# MCU.net
KiCad netlist of a schematic drawn in Altium Designer
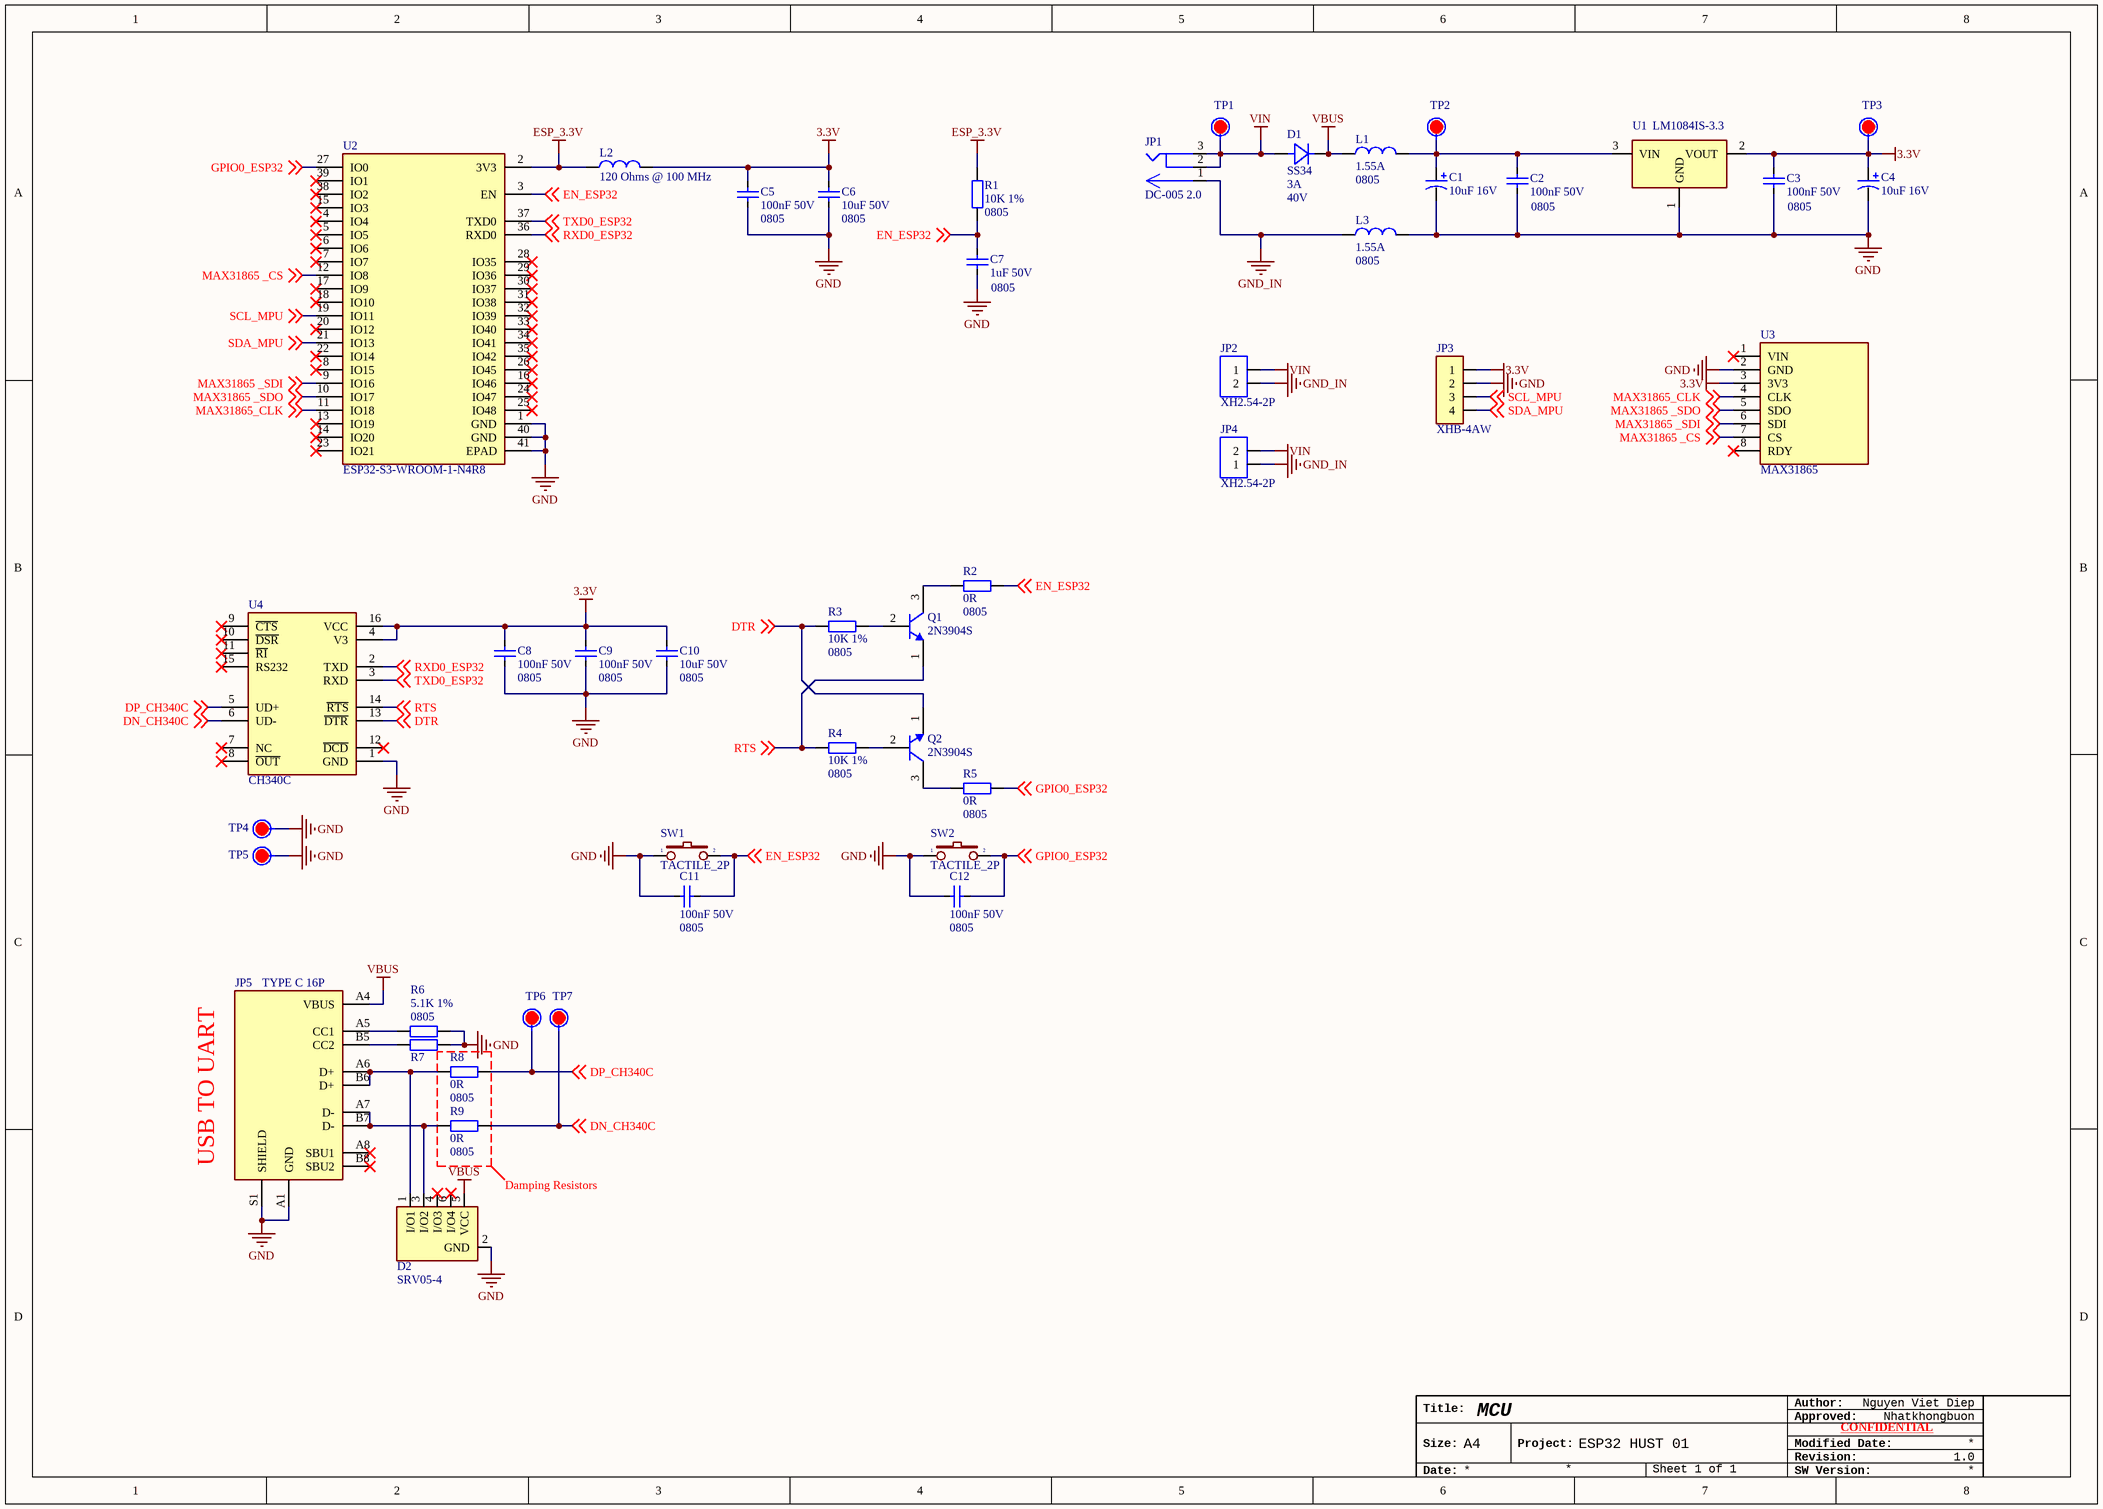
[diagram p0: MCU.SchDoc]

(export (version "E")
  (design (tool "Eeschema 10.0.6"))
  (components
    (comp (ref "C1")
      (value "10uF 16V")
      (footprint "CAP-ALU-SMD-B -NEW")
      (description "10uF 16V 14mA@120Hz ±20% SMD,D4xL5.4mm Aluminum Electrolytic Capacitors - SMD ROHS")
      (fields (field (name "MANUFACTURER") "KNSCHA") (field (name "MANUFACTURE PART NUMBER") "RST10UF16V013"))
      (libsource (lib "Capacitors") (part "C_ALU_10uF_16V_B"))
    )
    (comp (ref "C2")
      (value "100nF 50V")
      (footprint "CAP_SMD_0805_NEW")
      (description "0.1 µF ±10% 50V Ceramic Capacitor X7R 0805 (2012 Metric)")
      (fields
        (field (name "MANUFACTURER") "YAGEO")
        (field (name "MANUFACTURE PART NUMBER") "CC0805KRX7R9BB104")
        (field (name "SIZE") "0805")
      )
      (libsource (lib "Capacitors") (part "C0805_MLCC_100nF_50V"))
    )
    (comp (ref "C3")
      (value "100nF 50V")
      (footprint "CAP_SMD_0805_NEW")
      (description "0.1 µF ±10% 50V Ceramic Capacitor X7R 0805 (2012 Metric)")
      (fields
        (field (name "MANUFACTURER") "YAGEO")
        (field (name "MANUFACTURE PART NUMBER") "CC0805KRX7R9BB104")
        (field (name "SIZE") "0805")
      )
      (libsource (lib "Capacitors") (part "C0805_MLCC_100nF_50V"))
    )
    (comp (ref "C4")
      (value "10uF 16V")
      (footprint "CAP-ALU-SMD-B -NEW")
      (description "10uF 16V 14mA@120Hz ±20% SMD,D4xL5.4mm Aluminum Electrolytic Capacitors - SMD ROHS")
      (fields (field (name "MANUFACTURER") "KNSCHA") (field (name "MANUFACTURE PART NUMBER") "RST10UF16V013"))
      (libsource (lib "Capacitors") (part "C_ALU_10uF_16V_B"))
    )
    (comp (ref "C5")
      (value "100nF 50V")
      (footprint "CAP_SMD_0805_NEW")
      (description "0.1 µF ±10% 50V Ceramic Capacitor X7R 0805 (2012 Metric)")
      (fields
        (field (name "MANUFACTURER") "YAGEO")
        (field (name "MANUFACTURE PART NUMBER") "CC0805KRX7R9BB104")
        (field (name "SIZE") "0805")
      )
      (libsource (lib "Capacitors") (part "C0805_MLCC_100nF_50V"))
    )
    (comp (ref "C6")
      (value "10uF 50V")
      (footprint "CAP_SMD_0805_NEW")
      (description "10 µF ±20% 50V Ceramic Capacitor X5R 0805 (2012 Metric)")
      (fields
        (field (name "MANUFACTURER") "Murata Electronics")
        (field (name "MANUFACTURE PART NUMBER") "GRM21BR61H106ME43L")
        (field (name "SIZE") "0805")
      )
      (libsource (lib "Capacitors") (part "C0805_MLCC_10uF_50V"))
    )
    (comp (ref "C7")
      (value "1uF 50V")
      (footprint "CAP_SMD_0805_NEW")
      (description "1 µF ±10% 50V Ceramic Capacitor X7R 0805 (2012 Metric)")
      (fields
        (field (name "MANUFACTURER") "Samsung Electro-Mechanics")
        (field (name "MANUFACTURE PART NUMBER") "CL21B105KBFNNNG")
        (field (name "SIZE") "0805")
      )
      (libsource (lib "Capacitors") (part "C0805_MLCC_1uF_50V"))
    )
    (comp (ref "C8")
      (value "100nF 50V")
      (footprint "CAP_SMD_0805_NEW")
      (description "0.1 µF ±10% 50V Ceramic Capacitor X7R 0805 (2012 Metric)")
      (fields
        (field (name "MANUFACTURER") "YAGEO")
        (field (name "MANUFACTURE PART NUMBER") "CC0805KRX7R9BB104")
        (field (name "SIZE") "0805")
      )
      (libsource (lib "Capacitors") (part "C0805_MLCC_100nF_50V"))
    )
    (comp (ref "C9")
      (value "100nF 50V")
      (footprint "CAP_SMD_0805_NEW")
      (description "0.1 µF ±10% 50V Ceramic Capacitor X7R 0805 (2012 Metric)")
      (fields
        (field (name "MANUFACTURER") "YAGEO")
        (field (name "MANUFACTURE PART NUMBER") "CC0805KRX7R9BB104")
        (field (name "SIZE") "0805")
      )
      (libsource (lib "Capacitors") (part "C0805_MLCC_100nF_50V"))
    )
    (comp (ref "C10")
      (value "10uF 50V")
      (footprint "CAP_SMD_0805_NEW")
      (description "10 µF ±20% 50V Ceramic Capacitor X5R 0805 (2012 Metric)")
      (fields
        (field (name "MANUFACTURER") "Murata Electronics")
        (field (name "MANUFACTURE PART NUMBER") "GRM21BR61H106ME43L")
        (field (name "SIZE") "0805")
      )
      (libsource (lib "Capacitors") (part "C0805_MLCC_10uF_50V"))
    )
    (comp (ref "C11")
      (value "100nF 50V")
      (footprint "CAP_SMD_0805_NEW")
      (description "0.1 µF ±10% 50V Ceramic Capacitor X7R 0805 (2012 Metric)")
      (fields
        (field (name "MANUFACTURER") "YAGEO")
        (field (name "MANUFACTURE PART NUMBER") "CC0805KRX7R9BB104")
        (field (name "SIZE") "0805")
      )
      (libsource (lib "Capacitors") (part "C0805_MLCC_100nF_50V"))
    )
    (comp (ref "C12")
      (value "100nF 50V")
      (footprint "CAP_SMD_0805_NEW")
      (description "0.1 µF ±10% 50V Ceramic Capacitor X7R 0805 (2012 Metric)")
      (fields
        (field (name "MANUFACTURER") "YAGEO")
        (field (name "MANUFACTURE PART NUMBER") "CC0805KRX7R9BB104")
        (field (name "SIZE") "0805")
      )
      (libsource (lib "Capacitors") (part "C0805_MLCC_100nF_50V"))
    )
    (comp (ref "D1")
      (value "SS34")
      (footprint "SMA")
      (description "Diode 40 V 3A Surface Mount SMA")
      (fields
        (field (name "MANUFACTURER") "MDD")
        (field (name "CURRENT") "3A")
        (field (name "DC VOLTAGE") "40V")
      )
      (libsource (lib "Diode") (part "SS34"))
    )
    (comp (ref "D2")
      (value "SRV05-4")
      (footprint "SOT23-6")
      (description "15V Clamp 4A (8/20µs) Ipp Tvs Diode Surface Mount SOT23-6L")
      (fields (field (name "MANUFACTURER") "ANBON SEMICONDUCTOR (INT'L) LIMITED"))
      (libsource (lib "Diode") (part "TVS_SRV05-4"))
    )
    (comp (ref "JP1")
      (value "DC-005 2.0")
      (footprint "DC_POWER_JACK")
      (description "Right-Angle DC Power Receptacle 2mm 6.4mm Plugin DC Power Connector ROHS")
      (fields (field (name "MANUFACTURER") "BOOMELE(Boom Precision Elec)"))
      (libsource (lib "Connectors") (part "DC-005 2.0"))
    )
    (comp (ref "JP2")
      (value "XH2.54-2P")
      (footprint "XH_2.54_2P")
      (description "1x2P 2P XH 1 2.54mm Tin 2 -25℃~+85℃ Brass 3A Straight Plugin,P=2.54mm Wire To Board Connector ROHS")
      (fields
        (field (name "MANUFACTURER") "Megastar")
        (field (name "MANUFACTURE PART NUMBER") "ZX-XH2.54-2PZZ")
      )
      (libsource (lib "") (part "XH2.54-2P_1"))
    )
    (comp (ref "JP3")
      (value "XHB-4AW")
      (footprint "CONN_XHB-4AW")
      (description "1x4P 4P 1 2.5mm 4 Right-Angle Push-Pull,P=2.5mm Wire To Board Connector ROHS")
      (fields (field (name "MANUFACTURER") "BOOMELE(Boom Precision Elec)"))
      (libsource (lib "Connectors") (part "XHB-4AW"))
    )
    (comp (ref "JP4")
      (value "XH2.54-2P")
      (footprint "XH_2.54_2P")
      (description "1x2P 2P XH 1 2.54mm Tin 2 -25℃~+85℃ Brass 3A Straight Plugin,P=2.54mm Wire To Board Connector ROHS")
      (fields
        (field (name "MANUFACTURER") "Megastar")
        (field (name "MANUFACTURE PART NUMBER") "ZX-XH2.54-2PZZ")
      )
      (libsource (lib "Connectors") (part "XH2.54-2P"))
    )
    (comp (ref "JP5")
      (value "TYPE C 16P")
      (footprint "TYPE C 16P")
      (fields
        (field (name "MANUFACTURER") "Amphenol ICC (Commercial Products)")
        (field (name "MANUFACTURE PART NUMBER") "12402012E212A")
      )
      (libsource (lib "Connectors") (part "TYPE_C_16P"))
    )
    (comp (ref "L1")
      (value "120Ohms 100Mhz")
      (footprint "FB_0805")
      (fields
        (field (name "MANUFACTURER") "Murata Electronics")
        (field (name "MANUFACTURE PART NUMBER") "BLM21PG121BH1D")
        (field (name "CURRENT") "1.55A")
        (field (name "SIZE") "0805")
      )
      (libsource (lib "Inductors") (part "FR_120Ohms_100Mhz"))
    )
    (comp (ref "L2")
      (value "120Ohms 100Mhz")
      (footprint "FB_0805")
      (fields
        (field (name "MANUFACTURER") "Murata Electronics")
        (field (name "MANUFACTURE PART NUMBER") "BLM21PG121BH1D")
        (field (name "IMPEDANCE @ FREQUENCY") "120 Ohms @ 100 MHz")
      )
      (libsource (lib "Inductors") (part "FR_120Ohms_100Mhz"))
    )
    (comp (ref "L3")
      (value "120Ohms 100Mhz")
      (footprint "FB_0805")
      (fields
        (field (name "MANUFACTURER") "Murata Electronics")
        (field (name "MANUFACTURE PART NUMBER") "BLM21PG121BH1D")
        (field (name "CURRENT") "1.55A")
        (field (name "SIZE") "0805")
      )
      (libsource (lib "Inductors") (part "FR_120Ohms_100Mhz"))
    )
    (comp (ref "Q1")
      (value "2N3904S")
      (footprint "2N3904S")
      (description "40V 350mW 100@10mA,1V 200mA NPN SOT-23 Bipolar (BJT) ROHS")
      (fields
        (field (name "MANUFACTURER") "KEC Semicon")
        (field (name "MANUFACTURE PART NUMBER") "2N3904S-RTK/PS")
      )
      (libsource (lib "Trans_Fets") (part "2N3904S-RTK/PS"))
    )
    (comp (ref "Q2")
      (value "2N3904S")
      (footprint "2N3904S")
      (description "40V 350mW 100@10mA,1V 200mA NPN SOT-23 Bipolar (BJT) ROHS")
      (fields
        (field (name "MANUFACTURER") "KEC Semicon")
        (field (name "MANUFACTURE PART NUMBER") "2N3904S-RTK/PS")
      )
      (libsource (lib "Trans_Fets") (part "2N3904S-RTK/PS"))
    )
    (comp (ref "R1")
      (value "10K 1%")
      (footprint "RES_SMD_0805")
      (description "10 kOhms ±1% 0.125W, 1/8W Chip Resistor 0805 (2012 Metric) Moisture Resistant Thick Film")
      (fields
        (field (name "MANUFACTURER") "YAGEO")
        (field (name "MANUFACTURE PART NUMBER") "RC0805FR-0710KL")
        (field (name "SIZE") "0805")
      )
      (libsource (lib "Resistors") (part "R0805_10K"))
    )
    (comp (ref "R2")
      (value "0R")
      (footprint "RES_SMD_0805")
      (description "0 Ohms Jumper Chip Resistor 0805 (2012 Metric) Automotive AEC-Q200 Thick Film")
      (fields
        (field (name "MANUFACTURER") "Vishay Dale")
        (field (name "MANUFACTURE PART NUMBER") "CRCW08050000Z0EA")
        (field (name "SIZE") "0805")
      )
      (libsource (lib "Resistors") (part "R0805_0R"))
    )
    (comp (ref "R3")
      (value "10K 1%")
      (footprint "RES_SMD_0805")
      (description "10 kOhms ±1% 0.125W, 1/8W Chip Resistor 0805 (2012 Metric) Moisture Resistant Thick Film")
      (fields
        (field (name "MANUFACTURER") "YAGEO")
        (field (name "MANUFACTURE PART NUMBER") "RC0805FR-0710KL")
        (field (name "SIZE") "0805")
      )
      (libsource (lib "Resistors") (part "R0805_10K"))
    )
    (comp (ref "R4")
      (value "10K 1%")
      (footprint "RES_SMD_0805")
      (description "10 kOhms ±1% 0.125W, 1/8W Chip Resistor 0805 (2012 Metric) Moisture Resistant Thick Film")
      (fields
        (field (name "MANUFACTURER") "YAGEO")
        (field (name "MANUFACTURE PART NUMBER") "RC0805FR-0710KL")
        (field (name "SIZE") "0805")
      )
      (libsource (lib "Resistors") (part "R0805_10K"))
    )
    (comp (ref "R5")
      (value "0R")
      (footprint "RES_SMD_0805")
      (description "0 Ohms Jumper Chip Resistor 0805 (2012 Metric) Automotive AEC-Q200 Thick Film")
      (fields
        (field (name "MANUFACTURER") "Vishay Dale")
        (field (name "MANUFACTURE PART NUMBER") "CRCW08050000Z0EA")
        (field (name "SIZE") "0805")
      )
      (libsource (lib "Resistors") (part "R0805_0R"))
    )
    (comp (ref "R6")
      (value "5.1K 1%")
      (footprint "RES_SMD_0805")
      (description "5.1 kOhms ±1% 0.125W, 1/8W Chip Resistor 0805 (2012 Metric) Moisture Resistant Thick Film")
      (fields
        (field (name "MANUFACTURER") "YAGEO")
        (field (name "MANUFACTURE PART NUMBER") "RC0805FR-075K1L")
        (field (name "SIZE") "0805")
      )
      (libsource (lib "Resistors") (part "R0805_5.1K"))
    )
    (comp (ref "R7")
      (value "5.1K 1%")
      (footprint "RES_SMD_0805")
      (description "5.1 kOhms ±1% 0.125W, 1/8W Chip Resistor 0805 (2012 Metric) Moisture Resistant Thick Film")
      (fields
        (field (name "MANUFACTURER") "YAGEO")
        (field (name "MANUFACTURE PART NUMBER") "RC0805FR-075K1L")
      )
      (libsource (lib "Resistors") (part "R0805_5.1K"))
    )
    (comp (ref "R8")
      (value "0R")
      (footprint "RES_SMD_0805")
      (description "0 Ohms Jumper Chip Resistor 0805 (2012 Metric) Automotive AEC-Q200 Thick Film")
      (fields
        (field (name "MANUFACTURER") "Vishay Dale")
        (field (name "MANUFACTURE PART NUMBER") "CRCW08050000Z0EA")
        (field (name "SIZE") "0805")
      )
      (libsource (lib "Resistors") (part "R0805_0R"))
    )
    (comp (ref "R9")
      (value "0R")
      (footprint "RES_SMD_0805")
      (description "0 Ohms Jumper Chip Resistor 0805 (2012 Metric) Automotive AEC-Q200 Thick Film")
      (fields
        (field (name "MANUFACTURER") "Vishay Dale")
        (field (name "MANUFACTURE PART NUMBER") "CRCW08050000Z0EA")
        (field (name "SIZE") "0805")
      )
      (libsource (lib "Resistors") (part "R0805_0R"))
    )
    (comp (ref "SW1")
      (value "TACTILE_2P")
      (footprint "C&K SW 2P")
      (description "Tactile Switch SPST-NO Top Actuated Surface Mount")
      (fields
        (field (name "MANUFACTURER") "C&K")
        (field (name "MANUFACTURE PART NUMBER") "PTS636 SM25F SMTR LFS")
      )
      (libsource (lib "Button") (part "SWITCH_TACTILE_SPST"))
    )
    (comp (ref "SW2")
      (value "TACTILE_2P")
      (footprint "C&K SW 2P")
      (description "Tactile Switch SPST-NO Top Actuated Surface Mount")
      (fields
        (field (name "MANUFACTURER") "C&K")
        (field (name "MANUFACTURE PART NUMBER") "PTS636 SM25F SMTR LFS")
      )
      (libsource (lib "Button") (part "SWITCH_TACTILE_SPST"))
    )
    (comp (ref "TP1")
      (value "Test Point")
      (footprint "TEST_POINT")
      (libsource (lib "Connectors") (part "TEST_POINT"))
    )
    (comp (ref "TP2")
      (value "Test Point")
      (footprint "TEST_POINT")
      (libsource (lib "Connectors") (part "TEST_POINT"))
    )
    (comp (ref "TP3")
      (value "Test Point")
      (footprint "TEST_POINT")
      (libsource (lib "Connectors") (part "TEST_POINT"))
    )
    (comp (ref "TP4")
      (value "Test Point")
      (footprint "TEST_POINT")
      (libsource (lib "Connectors") (part "TEST_POINT"))
    )
    (comp (ref "TP5")
      (value "Test Point")
      (footprint "TEST_POINT")
      (libsource (lib "Connectors") (part "TEST_POINT"))
    )
    (comp (ref "TP6")
      (value "Test Point")
      (footprint "TEST_POINT")
      (libsource (lib "Connectors") (part "TEST_POINT"))
    )
    (comp (ref "TP7")
      (value "Test Point")
      (footprint "TEST_POINT")
      (libsource (lib "Connectors") (part "TEST_POINT"))
    )
    (comp (ref "U1")
      (value "LM1084IS-3.3")
      (footprint "TO263")
      (description "Linear Voltage Regulator IC Positive Fixed 1 Output 5A TO-263 (DDPAK-3)")
      (fields
        (field (name "MANUFACTURER") "STMicroelectronics")
        (field (name "MANUFACTURE PART NUMBER") "LM1084IS-3.3/NOPB")
      )
      (libsource (lib "Voltage_Regulators") (part "LM1084IS-3.3"))
    )
    (comp (ref "U2")
      (value "ESP32-S3-WROOM-1-N4R8")
      (footprint "ESP32-S3-WROOM-1-N4R8")
      (description "Bluetooth, WiFi 802.11b/g/n, Bluetooth v5.0 Transceiver Module 2.4GHz PCB Trace Surface Mount")
      (fields (field (name "MANUFACTURER") "Espressif Systems"))
      (libsource (lib "MCU") (part "ESP32-S3-WROOM-1-N4R8"))
    )
    (comp (ref "U3")
      (value "MAX31865")
      (footprint "MAX31865 - 3")
      (description "Mạch chuyển tín hiệu RTD to Digital MAX31865 PT100/PT1000")
      (libsource (lib "Modules") (part "MAX31865"))
    )
    (comp (ref "U4")
      (value "CH340C")
      (footprint "CH340C")
      (description "2Mbps Transceiver USB 2.0 SOP-16 USB Converters ROHS")
      (fields (field (name "MANUFACTURER") "WCH(Jiangsu Qin Heng)"))
      (libsource (lib "ICs") (part "CH340C"))
    )
  )
  (nets
    (net (code "1") (name "3.3V") (class "Default")
      (node (ref "C10") (pin "2") (pinfunction "2_2") (pintype "passive"))
      (node (ref "C3") (pin "2") (pinfunction "2_2") (pintype "passive"))
      (node (ref "C4") (pin "1") (pinfunction "1_1") (pintype "passive"))
      (node (ref "C5") (pin "2") (pinfunction "2_2") (pintype "passive"))
      (node (ref "C6") (pin "2") (pinfunction "2_2") (pintype "passive"))
      (node (ref "C8") (pin "2") (pinfunction "2_2") (pintype "passive"))
      (node (ref "C9") (pin "2") (pinfunction "2_2") (pintype "passive"))
      (node (ref "JP3") (pin "1") (pinfunction "1_1") (pintype "passive"))
      (node (ref "L2") (pin "2") (pinfunction "2_2") (pintype "passive"))
      (node (ref "TP3") (pin "1") (pinfunction "1_1") (pintype "passive"))
      (node (ref "U1") (pin "2") (pinfunction "VOUT_2") (pintype "passive"))
      (node (ref "U3") (pin "3") (pinfunction "3V3_3") (pintype "passive"))
      (node (ref "U4") (pin "16") (pinfunction "VCC_16") (pintype "passive"))
      (node (ref "U4") (pin "4") (pinfunction "V3_4") (pintype "passive"))
    )
    (net (code "2") (name "DN_CH340C") (class "Default")
      (node (ref "R9") (pin "2") (pinfunction "2_2") (pintype "passive"))
      (node (ref "TP7") (pin "1") (pinfunction "1_1") (pintype "passive"))
      (node (ref "U4") (pin "6") (pinfunction "UD-_6") (pintype "passive"))
    )
    (net (code "3") (name "DP_CH340C") (class "Default")
      (node (ref "R8") (pin "2") (pinfunction "2_2") (pintype "passive"))
      (node (ref "TP6") (pin "1") (pinfunction "1_1") (pintype "passive"))
      (node (ref "U4") (pin "5") (pinfunction "UD+_5") (pintype "passive"))
    )
    (net (code "4") (name "DTR") (class "Default")
      (node (ref "Q2") (pin "1") (pinfunction "B_1") (pintype "passive"))
      (node (ref "R3") (pin "2") (pinfunction "2_2") (pintype "passive"))
      (node (ref "U4") (pin "13") (pinfunction "~{DTR}_13") (pintype "passive"))
    )
    (net (code "5") (name "EN_ESP32") (class "Default")
      (node (ref "C11") (pin "1") (pinfunction "1_1") (pintype "passive"))
      (node (ref "C7") (pin "2") (pinfunction "2_2") (pintype "passive"))
      (node (ref "R1") (pin "1") (pinfunction "1_1") (pintype "passive"))
      (node (ref "R2") (pin "2") (pinfunction "2_2") (pintype "passive"))
      (node (ref "SW1") (pin "2") (pinfunction "2_2") (pintype "passive"))
      (node (ref "U2") (pin "3") (pinfunction "EN_3") (pintype "passive"))
    )
    (net (code "6") (name "ESP_3.3V") (class "Default")
      (node (ref "L2") (pin "1") (pinfunction "1_1") (pintype "passive"))
      (node (ref "R1") (pin "2") (pinfunction "2_2") (pintype "passive"))
      (node (ref "U2") (pin "2") (pinfunction "3V3_2") (pintype "passive"))
    )
    (net (code "7") (name "GND") (class "Default")
      (node (ref "C1") (pin "2") (pinfunction "2_2") (pintype "passive"))
      (node (ref "C10") (pin "1") (pinfunction "1_1") (pintype "passive"))
      (node (ref "C11") (pin "2") (pinfunction "2_2") (pintype "passive"))
      (node (ref "C12") (pin "2") (pinfunction "2_2") (pintype "passive"))
      (node (ref "C2") (pin "1") (pinfunction "1_1") (pintype "passive"))
      (node (ref "C3") (pin "1") (pinfunction "1_1") (pintype "passive"))
      (node (ref "C4") (pin "2") (pinfunction "2_2") (pintype "passive"))
      (node (ref "C5") (pin "1") (pinfunction "1_1") (pintype "passive"))
      (node (ref "C6") (pin "1") (pinfunction "1_1") (pintype "passive"))
      (node (ref "C7") (pin "1") (pinfunction "1_1") (pintype "passive"))
      (node (ref "C8") (pin "1") (pinfunction "1_1") (pintype "passive"))
      (node (ref "C9") (pin "1") (pinfunction "1_1") (pintype "passive"))
      (node (ref "D2") (pin "2") (pinfunction "GND_2") (pintype "passive"))
      (node (ref "JP3") (pin "2") (pinfunction "2_2") (pintype "passive"))
      (node (ref "JP5") (pin "A1") (pinfunction "GND_A1") (pintype "passive"))
      (node (ref "JP5") (pin "S1") (pinfunction "SHIELD_S1") (pintype "passive"))
      (node (ref "L3") (pin "2") (pinfunction "2_2") (pintype "passive"))
      (node (ref "R6") (pin "2") (pinfunction "2_2") (pintype "passive"))
      (node (ref "R7") (pin "2") (pinfunction "2_2") (pintype "passive"))
      (node (ref "SW1") (pin "1") (pinfunction "1_1") (pintype "passive"))
      (node (ref "SW2") (pin "1") (pinfunction "1_1") (pintype "passive"))
      (node (ref "TP4") (pin "1") (pinfunction "1_1") (pintype "passive"))
      (node (ref "TP5") (pin "1") (pinfunction "1_1") (pintype "passive"))
      (node (ref "U1") (pin "1") (pinfunction "GND_1") (pintype "passive"))
      (node (ref "U2") (pin "1") (pinfunction "GND_1") (pintype "passive"))
      (node (ref "U2") (pin "40") (pinfunction "GND_40") (pintype "passive"))
      (node (ref "U2") (pin "41") (pinfunction "EPAD_41") (pintype "passive"))
      (node (ref "U3") (pin "2") (pinfunction "GND_2") (pintype "passive"))
      (node (ref "U4") (pin "1") (pinfunction "GND_1") (pintype "passive"))
    )
    (net (code "8") (name "GND_IN") (class "Default")
      (node (ref "JP1") (pin "1") (pinfunction "1_1") (pintype "passive"))
      (node (ref "JP2") (pin "2") (pinfunction "2_2") (pintype "passive"))
      (node (ref "JP4") (pin "1") (pinfunction "1_1") (pintype "passive"))
      (node (ref "L3") (pin "1") (pinfunction "1_1") (pintype "passive"))
    )
    (net (code "9") (name "GPIO0_ESP32") (class "Default")
      (node (ref "C12") (pin "1") (pinfunction "1_1") (pintype "passive"))
      (node (ref "R5") (pin "2") (pinfunction "2_2") (pintype "passive"))
      (node (ref "SW2") (pin "2") (pinfunction "2_2") (pintype "passive"))
      (node (ref "U2") (pin "27") (pinfunction "IO0_27") (pintype "passive"))
    )
    (net (code "10") (name "MAX31865 _CS") (class "Default")
      (node (ref "U2") (pin "12") (pinfunction "IO8_12") (pintype "passive"))
      (node (ref "U3") (pin "7") (pinfunction "CS_7") (pintype "passive"))
    )
    (net (code "11") (name "MAX31865 _SDI") (class "Default")
      (node (ref "U2") (pin "9") (pinfunction "IO16_9") (pintype "passive"))
      (node (ref "U3") (pin "6") (pinfunction "SDI_6") (pintype "passive"))
    )
    (net (code "12") (name "MAX31865 _SDO") (class "Default")
      (node (ref "U2") (pin "10") (pinfunction "IO17_10") (pintype "passive"))
      (node (ref "U3") (pin "5") (pinfunction "SDO_5") (pintype "passive"))
    )
    (net (code "13") (name "MAX31865_CLK") (class "Default")
      (node (ref "U2") (pin "11") (pinfunction "IO18_11") (pintype "passive"))
      (node (ref "U3") (pin "4") (pinfunction "CLK_4") (pintype "passive"))
    )
    (net (code "14") (name "Net-(D2-I{slash}O1)") (class "Default")
      (node (ref "D2") (pin "1") (pinfunction "I/O1_1") (pintype "passive"))
      (node (ref "JP5") (pin "A6") (pinfunction "D+_A6") (pintype "passive"))
      (node (ref "JP5") (pin "B6") (pinfunction "D+_B6") (pintype "passive"))
      (node (ref "R8") (pin "1") (pinfunction "1_1") (pintype "passive"))
    )
    (net (code "15") (name "Net-(D2-I{slash}O2)") (class "Default")
      (node (ref "D2") (pin "3") (pinfunction "I/O2_3") (pintype "passive"))
      (node (ref "JP5") (pin "A7") (pinfunction "D-_A7") (pintype "passive"))
      (node (ref "JP5") (pin "B7") (pinfunction "D-_B7") (pintype "passive"))
      (node (ref "R9") (pin "1") (pinfunction "1_1") (pintype "passive"))
    )
    (net (code "16") (name "Net-(JP5-CC1)") (class "Default")
      (node (ref "JP5") (pin "A5") (pinfunction "CC1_A5") (pintype "passive"))
      (node (ref "R6") (pin "1") (pinfunction "1_1") (pintype "passive"))
    )
    (net (code "17") (name "Net-(JP5-CC2)") (class "Default")
      (node (ref "JP5") (pin "B5") (pinfunction "CC2_B5") (pintype "passive"))
      (node (ref "R7") (pin "1") (pinfunction "1_1") (pintype "passive"))
    )
    (net (code "18") (name "Net-(Q1-C)") (class "Default")
      (node (ref "Q1") (pin "3") (pinfunction "C_3") (pintype "passive"))
      (node (ref "R2") (pin "1") (pinfunction "1_1") (pintype "passive"))
    )
    (net (code "19") (name "Net-(Q1-E)") (class "Default")
      (node (ref "Q1") (pin "2") (pinfunction "E_2") (pintype "passive"))
      (node (ref "R3") (pin "1") (pinfunction "1_1") (pintype "passive"))
    )
    (net (code "20") (name "Net-(Q2-C)") (class "Default")
      (node (ref "Q2") (pin "3") (pinfunction "C_3") (pintype "passive"))
      (node (ref "R5") (pin "1") (pinfunction "1_1") (pintype "passive"))
    )
    (net (code "21") (name "Net-(Q2-E)") (class "Default")
      (node (ref "Q2") (pin "2") (pinfunction "E_2") (pintype "passive"))
      (node (ref "R4") (pin "1") (pinfunction "1_1") (pintype "passive"))
    )
    (net (code "22") (name "Net-(U1-VIN)") (class "Default")
      (node (ref "C1") (pin "1") (pinfunction "1_1") (pintype "passive"))
      (node (ref "C2") (pin "2") (pinfunction "2_2") (pintype "passive"))
      (node (ref "L1") (pin "2") (pinfunction "2_2") (pintype "passive"))
      (node (ref "TP2") (pin "1") (pinfunction "1_1") (pintype "passive"))
      (node (ref "U1") (pin "3") (pinfunction "VIN_3") (pintype "passive"))
    )
    (net (code "23") (name "RTS") (class "Default")
      (node (ref "Q1") (pin "1") (pinfunction "B_1") (pintype "passive"))
      (node (ref "R4") (pin "2") (pinfunction "2_2") (pintype "passive"))
      (node (ref "U4") (pin "14") (pinfunction "~{RTS}_14") (pintype "passive"))
    )
    (net (code "24") (name "RXD0_ESP32") (class "Default")
      (node (ref "U2") (pin "36") (pinfunction "RXD0_36") (pintype "passive"))
      (node (ref "U4") (pin "2") (pinfunction "TXD_2") (pintype "passive"))
    )
    (net (code "25") (name "SCL_MPU") (class "Default")
      (node (ref "JP3") (pin "3") (pinfunction "3_3") (pintype "passive"))
      (node (ref "U2") (pin "19") (pinfunction "IO11_19") (pintype "passive"))
    )
    (net (code "26") (name "SDA_MPU") (class "Default")
      (node (ref "JP3") (pin "4") (pinfunction "4_4") (pintype "passive"))
      (node (ref "U2") (pin "21") (pinfunction "IO13_21") (pintype "passive"))
    )
    (net (code "27") (name "TXD0_ESP32") (class "Default")
      (node (ref "U2") (pin "37") (pinfunction "TXD0_37") (pintype "passive"))
      (node (ref "U4") (pin "3") (pinfunction "RXD_3") (pintype "passive"))
    )
    (net (code "28") (name "VBUS") (class "Default")
      (node (ref "D1") (pin "C") (pinfunction "C_C") (pintype "passive"))
      (node (ref "D2") (pin "5") (pinfunction "VCC_5") (pintype "passive"))
      (node (ref "JP5") (pin "A4") (pinfunction "VBUS_A4") (pintype "passive"))
      (node (ref "L1") (pin "1") (pinfunction "1_1") (pintype "passive"))
    )
    (net (code "29") (name "VIN") (class "Default")
      (node (ref "D1") (pin "A") (pinfunction "A_A") (pintype "passive"))
      (node (ref "JP1") (pin "2") (pinfunction "2_2") (pintype "passive"))
      (node (ref "JP1") (pin "3") (pinfunction "3_3") (pintype "passive"))
      (node (ref "JP2") (pin "1") (pinfunction "1_1") (pintype "passive"))
      (node (ref "JP4") (pin "2") (pinfunction "2_2") (pintype "passive"))
      (node (ref "TP1") (pin "1") (pinfunction "1_1") (pintype "passive"))
    )
    (net (code "30") (name "unconnected-(D2-I{slash}O3-Pad4)") (class "Default")
      (node (ref "D2") (pin "4") (pinfunction "I/O3_4") (pintype "passive+no_connect"))
    )
    (net (code "31") (name "unconnected-(D2-I{slash}O4-Pad6)") (class "Default")
      (node (ref "D2") (pin "6") (pinfunction "I/O4_6") (pintype "passive+no_connect"))
    )
    (net (code "32") (name "unconnected-(JP5-SBU1-PadA8)") (class "Default")
      (node (ref "JP5") (pin "A8") (pinfunction "SBU1_A8") (pintype "passive+no_connect"))
    )
    (net (code "33") (name "unconnected-(JP5-SBU2-PadB8)") (class "Default")
      (node (ref "JP5") (pin "B8") (pinfunction "SBU2_B8") (pintype "passive+no_connect"))
    )
    (net (code "34") (name "unconnected-(U2-IO1-Pad39)") (class "Default")
      (node (ref "U2") (pin "39") (pinfunction "IO1_39") (pintype "passive+no_connect"))
    )
    (net (code "35") (name "unconnected-(U2-IO2-Pad38)") (class "Default")
      (node (ref "U2") (pin "38") (pinfunction "IO2_38") (pintype "passive+no_connect"))
    )
    (net (code "36") (name "unconnected-(U2-IO3-Pad15)") (class "Default")
      (node (ref "U2") (pin "15") (pinfunction "IO3_15") (pintype "passive+no_connect"))
    )
    (net (code "37") (name "unconnected-(U2-IO4-Pad4)") (class "Default")
      (node (ref "U2") (pin "4") (pinfunction "IO4_4") (pintype "passive+no_connect"))
    )
    (net (code "38") (name "unconnected-(U2-IO5-Pad5)") (class "Default")
      (node (ref "U2") (pin "5") (pinfunction "IO5_5") (pintype "passive+no_connect"))
    )
    (net (code "39") (name "unconnected-(U2-IO6-Pad6)") (class "Default")
      (node (ref "U2") (pin "6") (pinfunction "IO6_6") (pintype "passive+no_connect"))
    )
    (net (code "40") (name "unconnected-(U2-IO7-Pad7)") (class "Default")
      (node (ref "U2") (pin "7") (pinfunction "IO7_7") (pintype "passive+no_connect"))
    )
    (net (code "41") (name "unconnected-(U2-IO9-Pad17)") (class "Default")
      (node (ref "U2") (pin "17") (pinfunction "IO9_17") (pintype "passive+no_connect"))
    )
    (net (code "42") (name "unconnected-(U2-IO10-Pad18)") (class "Default")
      (node (ref "U2") (pin "18") (pinfunction "IO10_18") (pintype "passive+no_connect"))
    )
    (net (code "43") (name "unconnected-(U2-IO12-Pad20)") (class "Default")
      (node (ref "U2") (pin "20") (pinfunction "IO12_20") (pintype "passive+no_connect"))
    )
    (net (code "44") (name "unconnected-(U2-IO14-Pad22)") (class "Default")
      (node (ref "U2") (pin "22") (pinfunction "IO14_22") (pintype "passive+no_connect"))
    )
    (net (code "45") (name "unconnected-(U2-IO15-Pad8)") (class "Default")
      (node (ref "U2") (pin "8") (pinfunction "IO15_8") (pintype "passive+no_connect"))
    )
    (net (code "46") (name "unconnected-(U2-IO19-Pad13)") (class "Default")
      (node (ref "U2") (pin "13") (pinfunction "IO19_13") (pintype "passive+no_connect"))
    )
    (net (code "47") (name "unconnected-(U2-IO20-Pad14)") (class "Default")
      (node (ref "U2") (pin "14") (pinfunction "IO20_14") (pintype "passive+no_connect"))
    )
    (net (code "48") (name "unconnected-(U2-IO21-Pad23)") (class "Default")
      (node (ref "U2") (pin "23") (pinfunction "IO21_23") (pintype "passive+no_connect"))
    )
    (net (code "49") (name "unconnected-(U2-IO35-Pad28)") (class "Default")
      (node (ref "U2") (pin "28") (pinfunction "IO35_28") (pintype "passive+no_connect"))
    )
    (net (code "50") (name "unconnected-(U2-IO36-Pad29)") (class "Default")
      (node (ref "U2") (pin "29") (pinfunction "IO36_29") (pintype "passive+no_connect"))
    )
    (net (code "51") (name "unconnected-(U2-IO37-Pad30)") (class "Default")
      (node (ref "U2") (pin "30") (pinfunction "IO37_30") (pintype "passive+no_connect"))
    )
    (net (code "52") (name "unconnected-(U2-IO38-Pad31)") (class "Default")
      (node (ref "U2") (pin "31") (pinfunction "IO38_31") (pintype "passive+no_connect"))
    )
    (net (code "53") (name "unconnected-(U2-IO39-Pad32)") (class "Default")
      (node (ref "U2") (pin "32") (pinfunction "IO39_32") (pintype "passive+no_connect"))
    )
    (net (code "54") (name "unconnected-(U2-IO40-Pad33)") (class "Default")
      (node (ref "U2") (pin "33") (pinfunction "IO40_33") (pintype "passive+no_connect"))
    )
    (net (code "55") (name "unconnected-(U2-IO41-Pad34)") (class "Default")
      (node (ref "U2") (pin "34") (pinfunction "IO41_34") (pintype "passive+no_connect"))
    )
    (net (code "56") (name "unconnected-(U2-IO42-Pad35)") (class "Default")
      (node (ref "U2") (pin "35") (pinfunction "IO42_35") (pintype "passive+no_connect"))
    )
    (net (code "57") (name "unconnected-(U2-IO45-Pad26)") (class "Default")
      (node (ref "U2") (pin "26") (pinfunction "IO45_26") (pintype "passive+no_connect"))
    )
    (net (code "58") (name "unconnected-(U2-IO46-Pad16)") (class "Default")
      (node (ref "U2") (pin "16") (pinfunction "IO46_16") (pintype "passive+no_connect"))
    )
    (net (code "59") (name "unconnected-(U2-IO47-Pad24)") (class "Default")
      (node (ref "U2") (pin "24") (pinfunction "IO47_24") (pintype "passive+no_connect"))
    )
    (net (code "60") (name "unconnected-(U2-IO48-Pad25)") (class "Default")
      (node (ref "U2") (pin "25") (pinfunction "IO48_25") (pintype "passive+no_connect"))
    )
    (net (code "61") (name "unconnected-(U3-RDY-Pad8)") (class "Default")
      (node (ref "U3") (pin "8") (pinfunction "RDY_8") (pintype "passive+no_connect"))
    )
    (net (code "62") (name "unconnected-(U3-VIN-Pad1)") (class "Default")
      (node (ref "U3") (pin "1") (pinfunction "VIN_1") (pintype "passive+no_connect"))
    )
    (net (code "63") (name "unconnected-(U4-NC-Pad7)") (class "Default")
      (node (ref "U4") (pin "7") (pinfunction "NC_7") (pintype "passive+no_connect"))
    )
    (net (code "64") (name "unconnected-(U4-RS232-Pad15)") (class "Default")
      (node (ref "U4") (pin "15") (pinfunction "RS232_15") (pintype "passive+no_connect"))
    )
    (net (code "65") (name "unconnected-(U4-~{CTS}-Pad9)") (class "Default")
      (node (ref "U4") (pin "9") (pinfunction "~{CTS}_9") (pintype "passive+no_connect"))
    )
    (net (code "66") (name "unconnected-(U4-~{DCD}-Pad12)") (class "Default")
      (node (ref "U4") (pin "12") (pinfunction "~{DCD}_12") (pintype "passive+no_connect"))
    )
    (net (code "67") (name "unconnected-(U4-~{DSR}-Pad10)") (class "Default")
      (node (ref "U4") (pin "10") (pinfunction "~{DSR}_10") (pintype "passive+no_connect"))
    )
    (net (code "68") (name "unconnected-(U4-~{OUT}-Pad8)") (class "Default")
      (node (ref "U4") (pin "8") (pinfunction "~{OUT}_8") (pintype "passive+no_connect"))
    )
    (net (code "69") (name "unconnected-(U4-~{RI}-Pad11)") (class "Default")
      (node (ref "U4") (pin "11") (pinfunction "~{RI}_11") (pintype "passive+no_connect"))
    )
  )
)
